# Power.net
KiCad netlist of a schematic drawn in Altium Designer
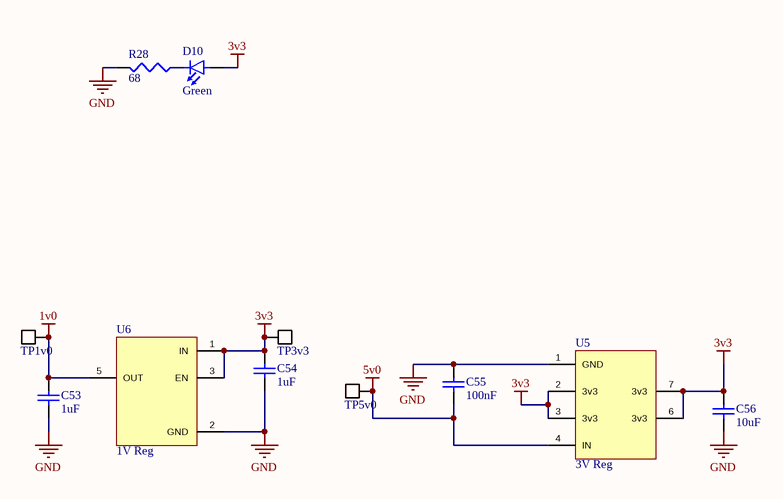
[diagram p0: Power.SchDoc]

(export (version "E")
  (design (tool "Eeschema 10.0.6"))
  (components
    (comp (ref "C53")
      (value "1uF")
      (footprint "SMD0603")
      (description "Ceramic Chip Capacitor")
      (fields (field (name "Comment") "Cap"))
      (libsource (lib "Components") (part "Capacitor Ceramic"))
    )
    (comp (ref "C54")
      (value "1uF")
      (footprint "SMD0603")
      (description "Ceramic Chip Capacitor")
      (fields (field (name "Comment") "Cap"))
      (libsource (lib "Components") (part "Capacitor Ceramic"))
    )
    (comp (ref "C55")
      (value "100nF")
      (footprint "SMD0603")
      (description "Ceramic Chip Capacitor")
      (fields (field (name "Comment") "Cap"))
      (libsource (lib "Components") (part "Capacitor Ceramic"))
    )
    (comp (ref "C56")
      (value "10uF")
      (footprint "SMD0603")
      (description "Ceramic Chip Capacitor")
      (fields (field (name "Comment") "Cap"))
      (libsource (lib "Components") (part "Capacitor Ceramic"))
    )
    (comp (ref "D10")
      (value "LED")
      (footprint "SMD0805_LED")
      (fields (field (name "COLOR") "Green"))
      (libsource (lib "Components") (part "LED"))
    )
    (comp (ref "R28")
      (value "68")
      (footprint "SMD0603")
      (description "Resistor")
      (fields (field (name "Comment") "Res"))
      (libsource (lib "Components") (part "Resistor"))
    )
    (comp (ref "TP1v0")
      (value "Test Point")
      (footprint "Test Point")
      (libsource (lib "Components") (part "Test Point"))
    )
    (comp (ref "TP3v3")
      (value "Test Point")
      (footprint "Test Point")
      (libsource (lib "Components") (part "Test Point"))
    )
    (comp (ref "TP5v0")
      (value "Test Point")
      (footprint "Test Point")
      (libsource (lib "Components") (part "Test Point"))
    )
    (comp (ref "U5") (value "3V Reg") (footprint "SOIC8") (libsource (lib "SEM_BMS") (part "3V Reg")))
    (comp (ref "U6") (value "1V Reg") (footprint "SOT23-5Lead") (libsource (lib "SEM_BMS") (part "1V Reg")))
  )
  (nets
    (net (code "1") (name "1v0") (class "Default")
      (node (ref "C53") (pin "2") (pinfunction "2_2") (pintype "passive"))
      (node (ref "TP1v0") (pin "1") (pinfunction "1_1") (pintype "passive"))
      (node (ref "U6") (pin "5") (pinfunction "OUT_5") (pintype "passive"))
    )
    (net (code "2") (name "3v3") (class "Default")
      (node (ref "C54") (pin "2") (pinfunction "2_2") (pintype "passive"))
      (node (ref "C56") (pin "2") (pinfunction "2_2") (pintype "passive"))
      (node (ref "D10") (pin "1") (pinfunction "Anode_(+)_1") (pintype "passive"))
      (node (ref "TP3v3") (pin "1") (pinfunction "1_1") (pintype "passive"))
      (node (ref "U5") (pin "2") (pinfunction "3v3_2") (pintype "passive"))
      (node (ref "U5") (pin "3") (pinfunction "3v3_3") (pintype "passive"))
      (node (ref "U5") (pin "6") (pinfunction "3v3_6") (pintype "passive"))
      (node (ref "U5") (pin "7") (pinfunction "3v3_7") (pintype "passive"))
      (node (ref "U6") (pin "1") (pinfunction "IN_1") (pintype "passive"))
      (node (ref "U6") (pin "3") (pinfunction "EN_3") (pintype "passive"))
    )
    (net (code "3") (name "5v0") (class "Default")
      (node (ref "C55") (pin "1") (pinfunction "1_1") (pintype "passive"))
      (node (ref "TP5v0") (pin "1") (pinfunction "1_1") (pintype "passive"))
      (node (ref "U5") (pin "4") (pinfunction "IN_4") (pintype "passive"))
    )
    (net (code "4") (name "GND") (class "Default")
      (node (ref "C53") (pin "1") (pinfunction "1_1") (pintype "passive"))
      (node (ref "C54") (pin "1") (pinfunction "1_1") (pintype "passive"))
      (node (ref "C55") (pin "2") (pinfunction "2_2") (pintype "passive"))
      (node (ref "C56") (pin "1") (pinfunction "1_1") (pintype "passive"))
      (node (ref "R28") (pin "2") (pinfunction "2_2") (pintype "passive"))
      (node (ref "U5") (pin "1") (pinfunction "GND_1") (pintype "passive"))
      (node (ref "U6") (pin "2") (pinfunction "GND_2") (pintype "passive"))
    )
    (net (code "5") (name "Net-(D10-Cathode_(-))") (class "Default")
      (node (ref "D10") (pin "2") (pinfunction "Cathode_(-)_2") (pintype "passive"))
      (node (ref "R28") (pin "1") (pinfunction "1_1") (pintype "passive"))
    )
  )
)
